# BAHIA.net
KiCad netlist of a schematic drawn in EAGLE
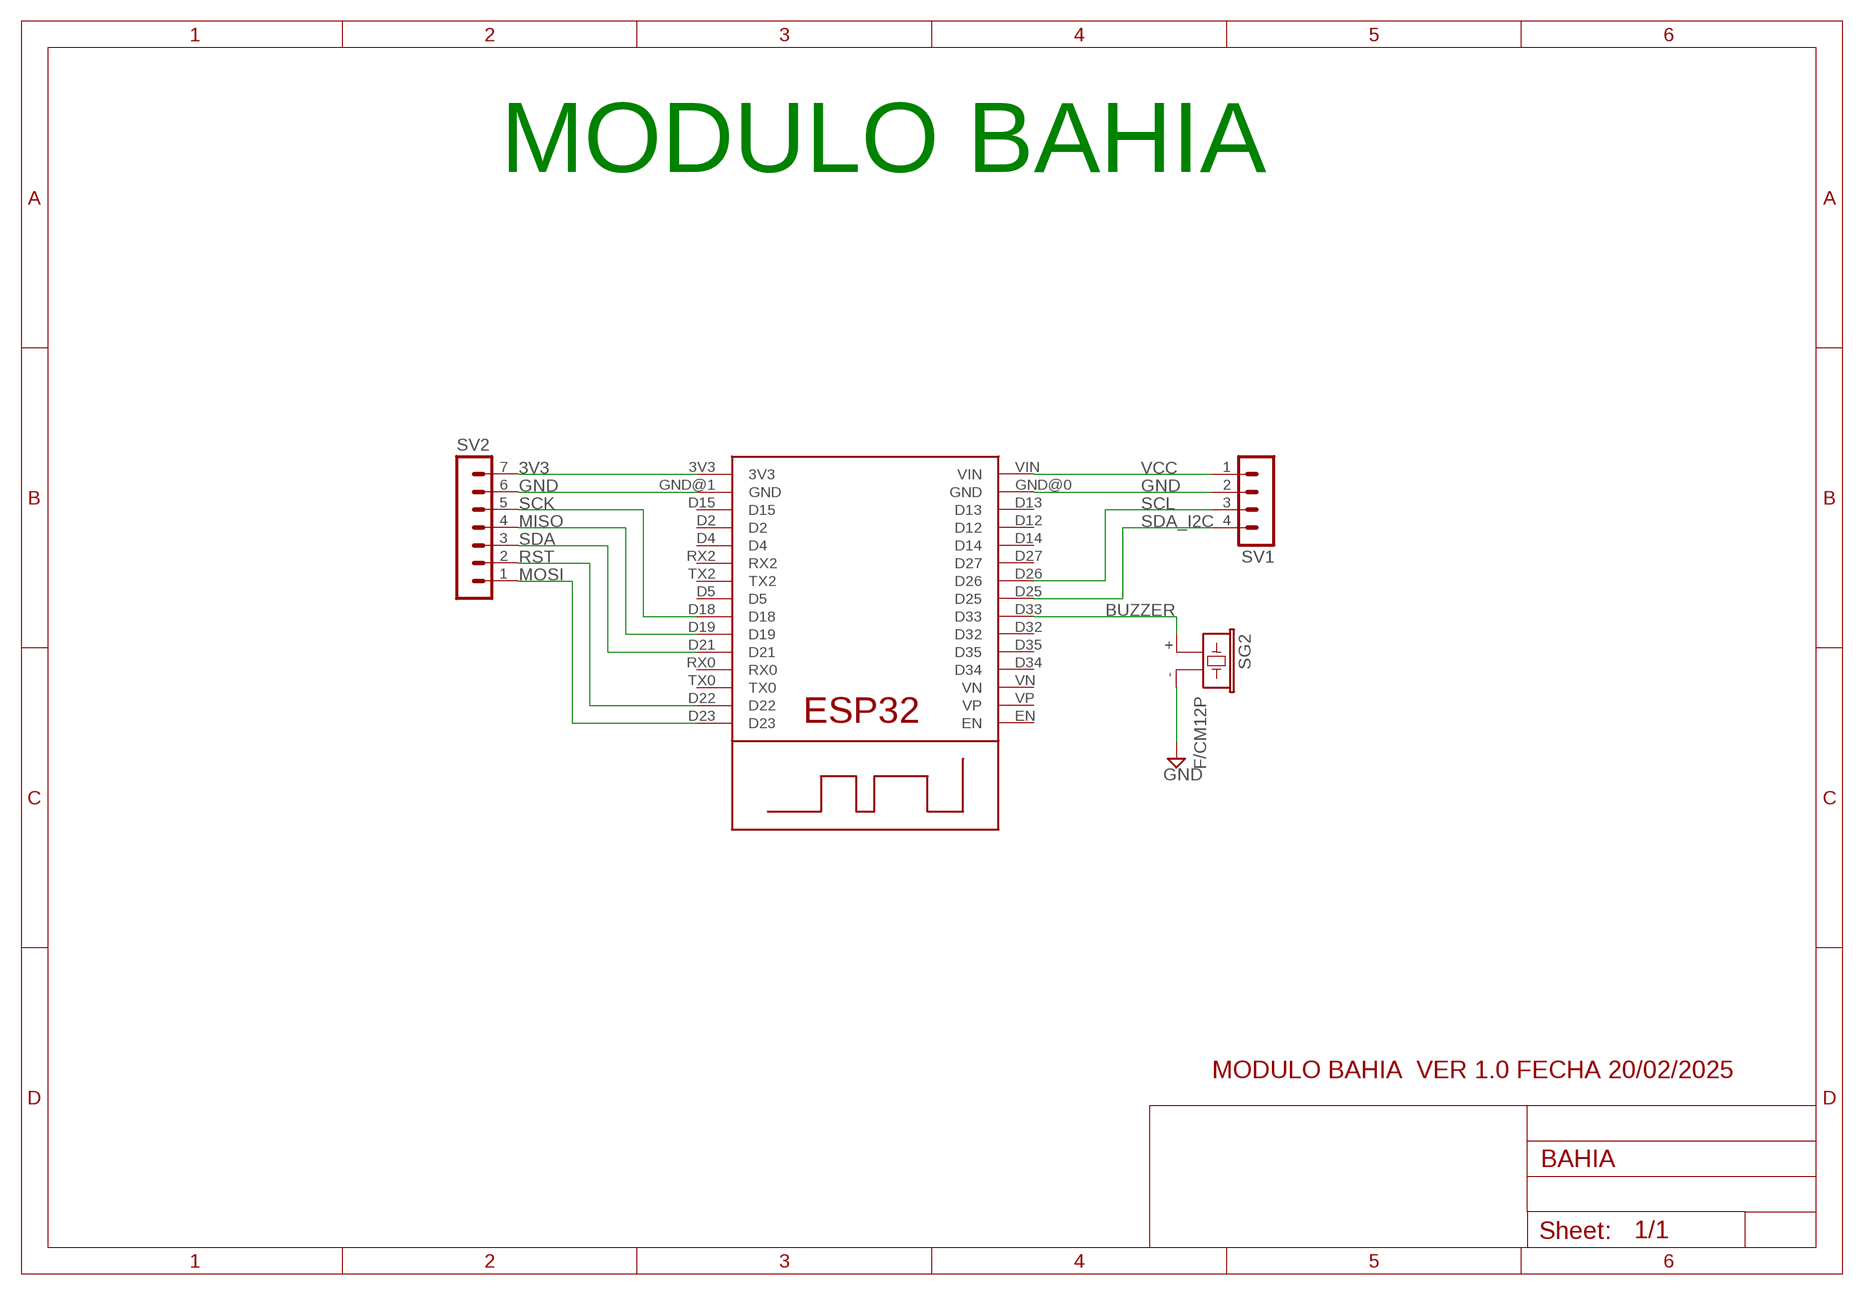
[diagram p0: schematic, sheet 1]

(export (version "E")
  (design (tool "Eeschema 10.0.6"))
  (components
    (comp (ref "SG2")
      (value "F/CM12P")
      (footprint "eagle-import:F_CM12P")
      (libsource (lib "eagle-import") (part "F/CM12P"))
    )
    (comp (ref "SV1")
      (value "MA04-1")
      (footprint "eagle-import:MA04-1")
      (libsource (lib "eagle-import") (part "MA04-1"))
    )
    (comp (ref "SV2")
      (value "MA07-1")
      (footprint "eagle-import:MA07-1")
      (libsource (lib "eagle-import") (part "MA07-1"))
    )
    (comp (ref "U$1")
      (value "ESP32WROOM")
      (footprint "eagle-import:ESP32WROOM")
      (libsource (lib "eagle-import") (part "ESP32WROOM"))
    )
  )
  (nets
    (net (code "1") (name "/3V3") (class "Default")
      (node (ref "SV2") (pin "7") (pinfunction "7_7") (pintype "passive"))
      (node (ref "U$1") (pin "3V3") (pinfunction "3V3_3V3") (pintype "bidirectional"))
    )
    (net (code "2") (name "/BUZZER") (class "Default")
      (node (ref "SG2") (pin "+") (pinfunction "1_+") (pintype "passive"))
      (node (ref "U$1") (pin "D33") (pinfunction "D33_D33") (pintype "bidirectional"))
    )
    (net (code "3") (name "/MISO") (class "Default")
      (node (ref "SV2") (pin "4") (pinfunction "4_4") (pintype "passive"))
      (node (ref "U$1") (pin "D19") (pinfunction "D19_D19") (pintype "bidirectional"))
    )
    (net (code "4") (name "/MOSI") (class "Default")
      (node (ref "SV2") (pin "1") (pinfunction "1_1") (pintype "passive"))
      (node (ref "U$1") (pin "D23") (pinfunction "D23_D23") (pintype "bidirectional"))
    )
    (net (code "5") (name "/RST") (class "Default")
      (node (ref "SV2") (pin "2") (pinfunction "2_2") (pintype "passive"))
      (node (ref "U$1") (pin "D22") (pinfunction "D22_D22") (pintype "bidirectional"))
    )
    (net (code "6") (name "/SCK") (class "Default")
      (node (ref "SV2") (pin "5") (pinfunction "5_5") (pintype "passive"))
      (node (ref "U$1") (pin "D18") (pinfunction "D18_D18") (pintype "bidirectional"))
    )
    (net (code "7") (name "/SCL") (class "Default")
      (node (ref "SV1") (pin "3") (pinfunction "3_3") (pintype "passive"))
      (node (ref "U$1") (pin "D26") (pinfunction "D26_D26") (pintype "bidirectional"))
    )
    (net (code "8") (name "/SDA") (class "Default")
      (node (ref "SV2") (pin "3") (pinfunction "3_3") (pintype "passive"))
      (node (ref "U$1") (pin "D21") (pinfunction "D21_D21") (pintype "bidirectional"))
    )
    (net (code "9") (name "/SDA_I2C") (class "Default")
      (node (ref "SV1") (pin "4") (pinfunction "4_4") (pintype "passive"))
      (node (ref "U$1") (pin "D25") (pinfunction "D25_D25") (pintype "bidirectional"))
    )
    (net (code "10") (name "/VCC") (class "Default")
      (node (ref "SV1") (pin "1") (pinfunction "1_1") (pintype "passive"))
      (node (ref "U$1") (pin "VIN") (pinfunction "VIN_VIN") (pintype "bidirectional"))
    )
    (net (code "11") (name "GND") (class "Default")
      (node (ref "SG2") (pin "-") (pinfunction "2_-") (pintype "passive"))
      (node (ref "SV1") (pin "2") (pinfunction "2_2") (pintype "passive"))
      (node (ref "SV2") (pin "6") (pinfunction "6_6") (pintype "passive"))
      (node (ref "U$1") (pin "GND@0") (pinfunction "GND_GND@0") (pintype "bidirectional"))
      (node (ref "U$1") (pin "GND@1") (pinfunction "GND_GND@1") (pintype "bidirectional"))
    )
    (net (code "12") (name "unconnected-(U$1-PadD2)") (class "Default")
      (node (ref "U$1") (pin "D2") (pinfunction "D2_D2") (pintype "bidirectional"))
    )
    (net (code "13") (name "unconnected-(U$1-PadD4)") (class "Default")
      (node (ref "U$1") (pin "D4") (pinfunction "D4_D4") (pintype "bidirectional"))
    )
    (net (code "14") (name "unconnected-(U$1-PadD5)") (class "Default")
      (node (ref "U$1") (pin "D5") (pinfunction "D5_D5") (pintype "bidirectional"))
    )
    (net (code "15") (name "unconnected-(U$1-PadD12)") (class "Default")
      (node (ref "U$1") (pin "D12") (pinfunction "D12_D12") (pintype "bidirectional"))
    )
    (net (code "16") (name "unconnected-(U$1-PadD13)") (class "Default")
      (node (ref "U$1") (pin "D13") (pinfunction "D13_D13") (pintype "bidirectional"))
    )
    (net (code "17") (name "unconnected-(U$1-PadD14)") (class "Default")
      (node (ref "U$1") (pin "D14") (pinfunction "D14_D14") (pintype "bidirectional"))
    )
    (net (code "18") (name "unconnected-(U$1-PadD15)") (class "Default")
      (node (ref "U$1") (pin "D15") (pinfunction "D15_D15") (pintype "bidirectional"))
    )
    (net (code "19") (name "unconnected-(U$1-PadD27)") (class "Default")
      (node (ref "U$1") (pin "D27") (pinfunction "D27_D27") (pintype "bidirectional"))
    )
    (net (code "20") (name "unconnected-(U$1-PadD32)") (class "Default")
      (node (ref "U$1") (pin "D32") (pinfunction "D32_D32") (pintype "bidirectional"))
    )
    (net (code "21") (name "unconnected-(U$1-PadD34)") (class "Default")
      (node (ref "U$1") (pin "D34") (pinfunction "D34_D34") (pintype "bidirectional"))
    )
    (net (code "22") (name "unconnected-(U$1-PadD35)") (class "Default")
      (node (ref "U$1") (pin "D35") (pinfunction "D35_D35") (pintype "bidirectional"))
    )
    (net (code "23") (name "unconnected-(U$1-PadEN)") (class "Default")
      (node (ref "U$1") (pin "EN") (pinfunction "EN_EN") (pintype "bidirectional"))
    )
    (net (code "24") (name "unconnected-(U$1-PadRX0)") (class "Default")
      (node (ref "U$1") (pin "RX0") (pinfunction "RX0_RX0") (pintype "bidirectional"))
    )
    (net (code "25") (name "unconnected-(U$1-PadRX2)") (class "Default")
      (node (ref "U$1") (pin "RX2") (pinfunction "RX2_RX2") (pintype "bidirectional"))
    )
    (net (code "26") (name "unconnected-(U$1-PadTX0)") (class "Default")
      (node (ref "U$1") (pin "TX0") (pinfunction "TX0_TX0") (pintype "bidirectional"))
    )
    (net (code "27") (name "unconnected-(U$1-PadTX2)") (class "Default")
      (node (ref "U$1") (pin "TX2") (pinfunction "TX2_TX2") (pintype "bidirectional"))
    )
    (net (code "28") (name "unconnected-(U$1-PadVN)") (class "Default")
      (node (ref "U$1") (pin "VN") (pinfunction "VN_VN") (pintype "bidirectional"))
    )
    (net (code "29") (name "unconnected-(U$1-PadVP)") (class "Default")
      (node (ref "U$1") (pin "VP") (pinfunction "VP_VP") (pintype "bidirectional"))
    )
  )
)
